# Bank_1.net
KiCad netlist of a schematic drawn in Altium Designer
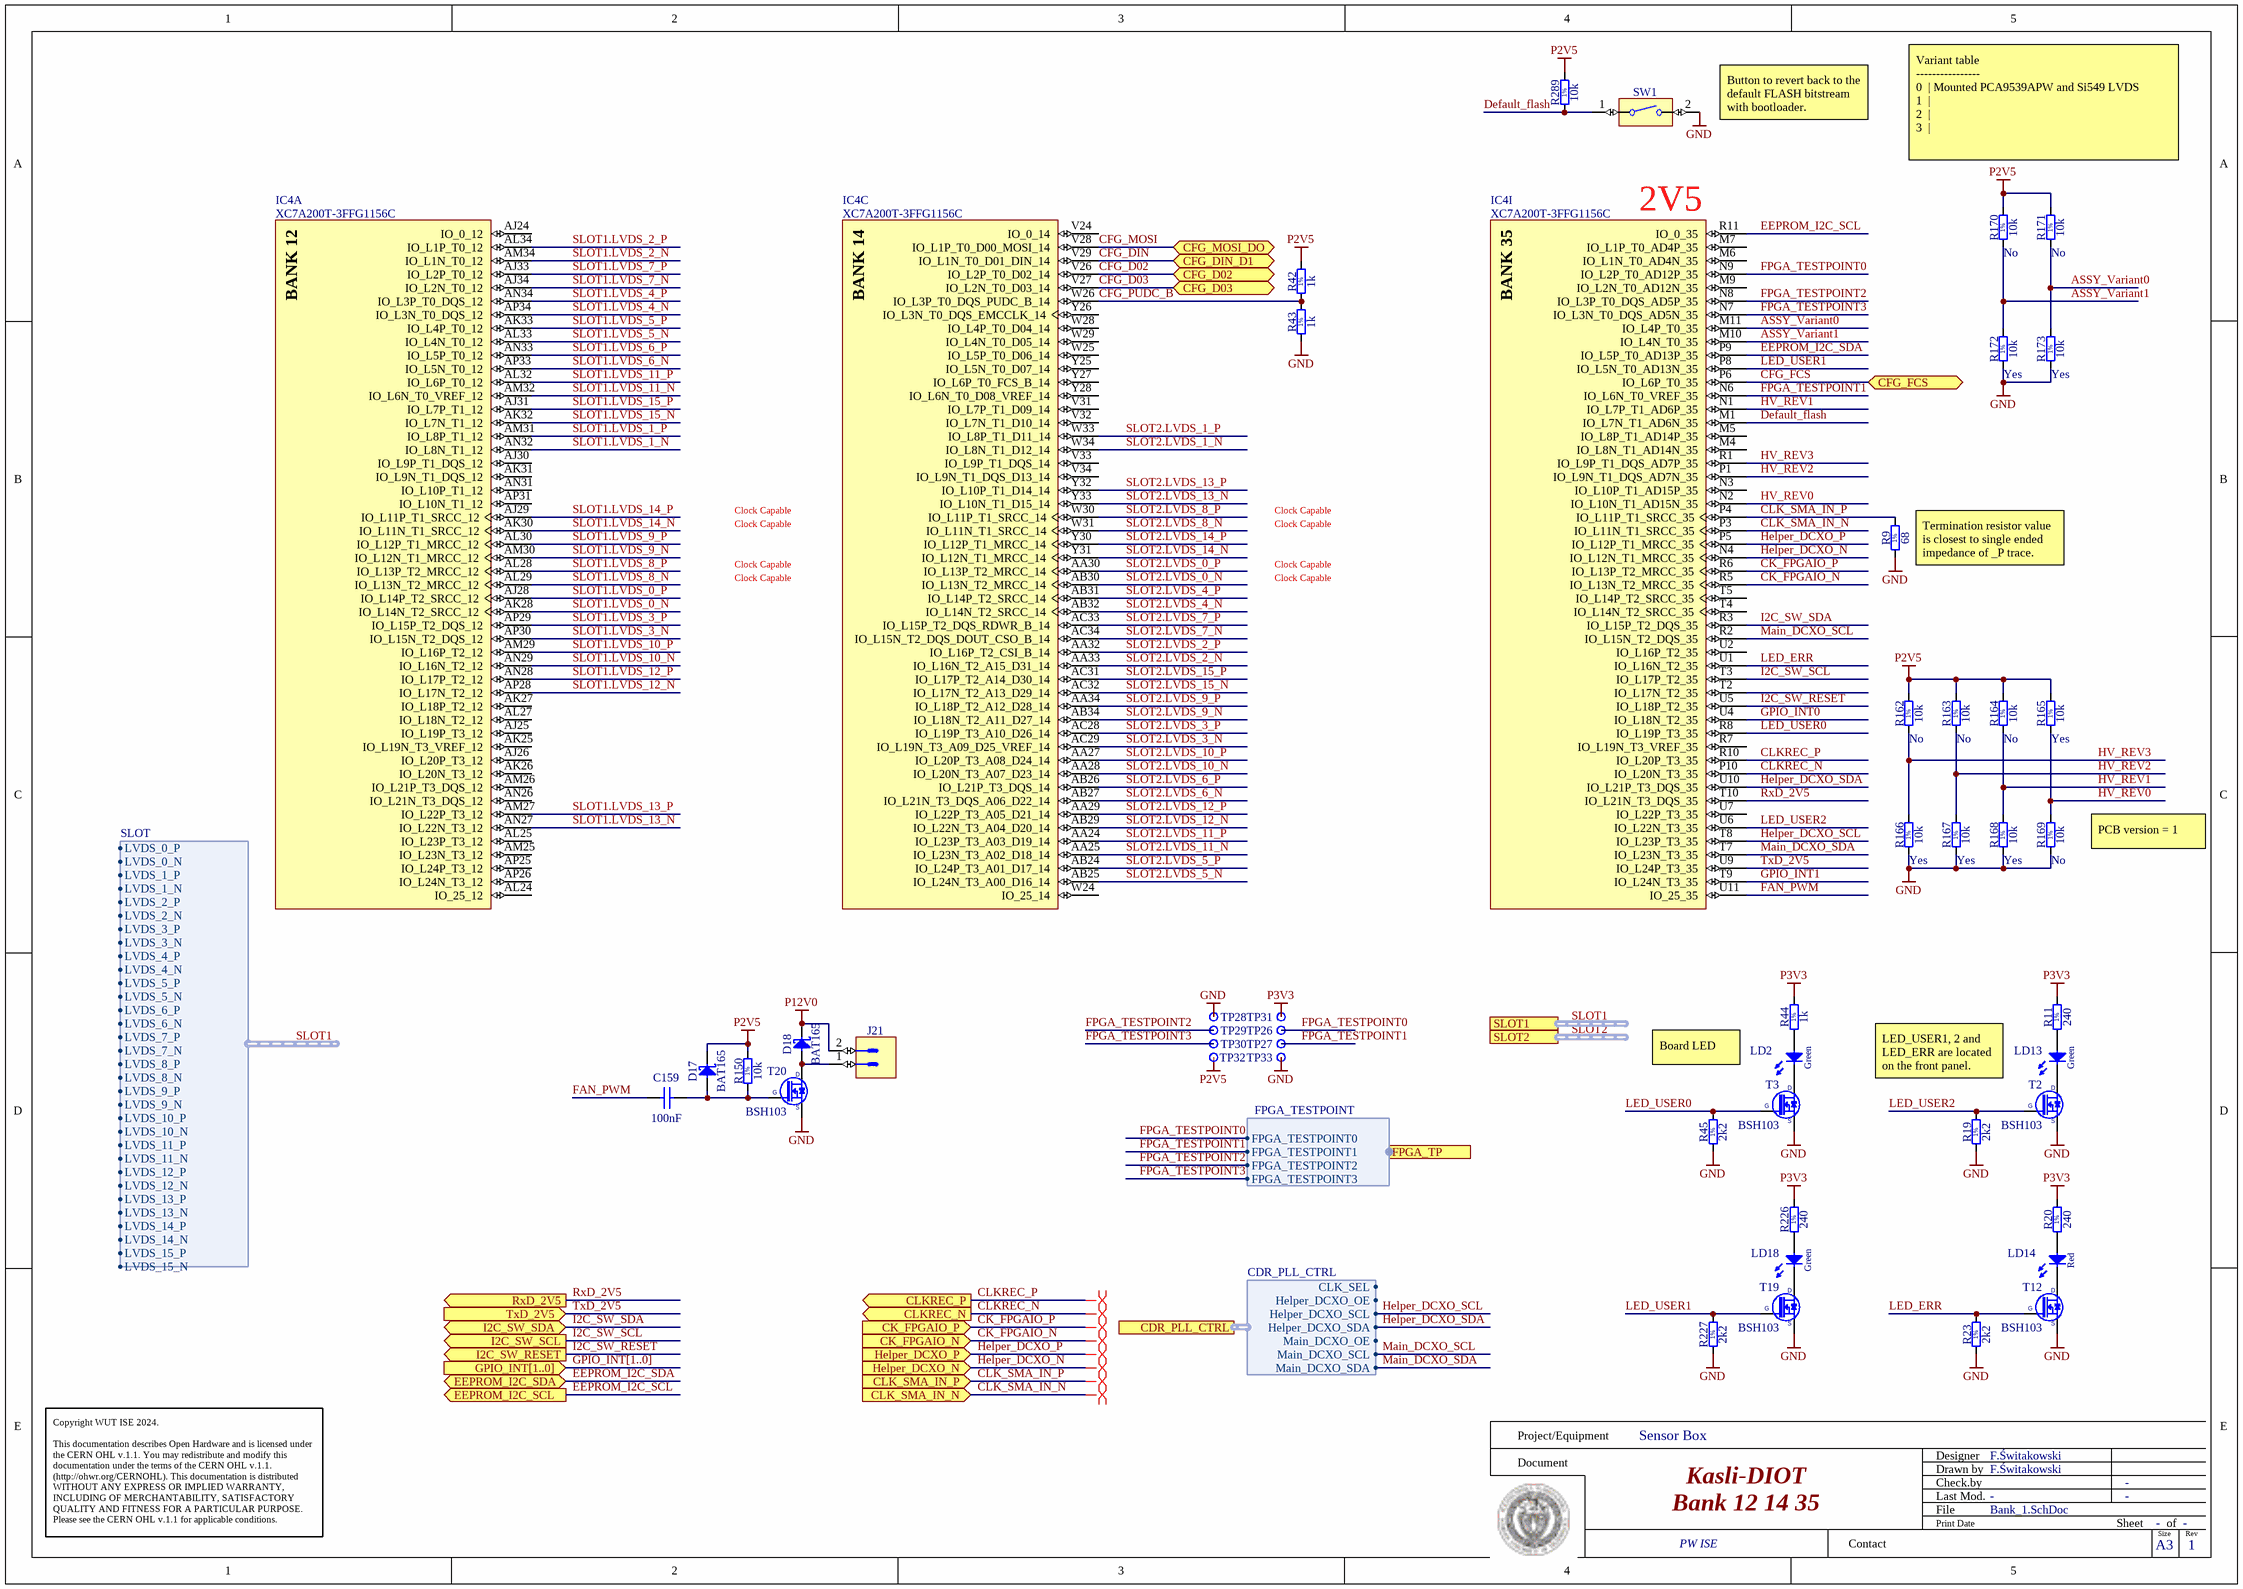
[diagram p0: Bank_1.SchDoc]

(export (version "E")
  (design (tool "Eeschema 10.0.6"))
  (components
    (comp (ref "C159")
      (value "100nF")
      (footprint "CAPC0603X33N")
      (description "Non-polarised capacitor")
      (fields
        (field (name "PART NUMBER") "CC0201_100NF_6.3V_10%_X5R")
        (field (name "VOLTAGE") "6.3V")
        (field (name "AUTHOR") "CERN DEM JLC")
      )
      (libsource (lib "Capacitors") (part "Capacitor - non polarized"))
    )
    (comp (ref "D17")
      (value "BAT165")
      (footprint "SOD2512X110N")
      (description "Schottky Diode")
      (fields
        (field (name "VOLTAGE") "40V")
        (field (name "POWER") "750mA")
        (field (name "AUTHOR") "CERN DEM JLC")
      )
      (libsource (lib "ICs And Semiconductors") (part "Diode Schottky"))
    )
    (comp (ref "D18")
      (value "BAT165")
      (footprint "SOD2512X110N")
      (description "Schottky Diode")
      (fields
        (field (name "VOLTAGE") "40V")
        (field (name "POWER") "750mA")
        (field (name "AUTHOR") "CERN DEM JLC")
      )
      (libsource (lib "ICs And Semiconductors") (part "Diode Schottky"))
    )
    (comp (ref "IC4")
      (value "XC7A200T-3FFG1156C")
      (footprint "BGA1156C100P34X34_3500X3500X310")
      (description "Artix-7 FPGA, 500 User I/Os, 16 GTP, 1156-Ball BGA, , Speed Grade 3, Commercial Grade, Pb-Free")
      (fields (field (name "MANUFACTURER") "XILINX") (field (name "AUTHOR") "CERN DEM JLC"))
      (libsource (lib "ICs And Semiconductors") (part "XC7A200T-3FFG1156C"))
    )
    (comp (ref "J21")
      (value "KK®")
      (footprint "MOLEX_22-27-2021")
      (description "Connector 2 Male")
      (fields
        (field (name "PART NUMBER") "MOLEX_22-27-2021")
        (field (name "MANUFACTURER") "MOLEX")
        (field (name "AUTHOR") "CERN DEM JLC")
      )
      (libsource (lib "Connectors") (part "Connector 2 Male"))
    )
    (comp (ref "LD2")
      (value "Green")
      (footprint "LED_KINGBRIGHT_KPH-1608CGCK")
      (description "LED Green 1C 2A")
      (fields
        (field (name "MANUFACTURER PART NUMBER") "KPH-1608CGCK")
        (field (name "PART NUMBER") "LED_KINGBRIGHT_KPH-1608CGCK")
        (field (name "AUTHOR") "CERN DEM JLC")
      )
      (libsource (lib "ICs And Semiconductors") (part "LED Green 1C 2A"))
    )
    (comp (ref "LD13")
      (value "Green")
      (footprint "LED_AVAGO_HSME-C120")
      (description "LED Green 1C 2A")
      (fields
        (field (name "MANUFACTURER PART NUMBER") "HSME-C120")
        (field (name "PART NUMBER") "LED_AVAGO_HSME-C120")
        (field (name "AUTHOR") "CERN DEM JMW")
      )
      (libsource (lib "ICs And Semiconductors") (part "LED Green 1C 2A"))
    )
    (comp (ref "LD14")
      (value "Red")
      (footprint "LED_AVAGO_HSMC-C120")
      (description "LED Red 1C 2A")
      (fields
        (field (name "MANUFACTURER PART NUMBER") "HSMC-C120")
        (field (name "PART NUMBER") "LED_AVAGO_HSMC-C120")
        (field (name "AUTHOR") "CERN DEM JMW")
      )
      (libsource (lib "ICs And Semiconductors") (part "LED Red 1C 2A"))
    )
    (comp (ref "LD18")
      (value "Green")
      (footprint "LED_AVAGO_HSME-C120")
      (description "LED Green 1C 2A")
      (fields
        (field (name "MANUFACTURER PART NUMBER") "HSME-C120")
        (field (name "PART NUMBER") "LED_AVAGO_HSME-C120")
        (field (name "AUTHOR") "CERN DEM JMW")
      )
      (libsource (lib "ICs And Semiconductors") (part "LED Green 1C 2A"))
    )
    (comp (ref "R9")
      (value "68")
      (footprint "RESC1005X40N")
      (description "Resistor - 1%")
      (fields
        (field (name "PART NUMBER") "R0402_68R_1%_0.0625W_100PPM")
        (field (name "POWER") "0.0625W")
        (field (name "AUTHOR") "CERN DEM JLC")
      )
      (libsource (lib "Resistors") (part "Resistor - 1%"))
    )
    (comp (ref "R11")
      (value "240")
      (footprint "RESC1005X40N")
      (description "Resistor - 1%")
      (fields
        (field (name "PART NUMBER") "R0402_240R_1%_0.0625W_100PPM")
        (field (name "POWER") "0.0625W")
        (field (name "AUTHOR") "CERN DEM JLC")
      )
      (libsource (lib "Resistors") (part "Resistor - 1%"))
    )
    (comp (ref "R19")
      (value "2k2")
      (footprint "RESC1005X40N")
      (description "Resistor - 1%")
      (fields
        (field (name "PART NUMBER") "R0402_2K2_1%_0.0625W_100PPM")
        (field (name "POWER") "0.0625W")
        (field (name "AUTHOR") "CERN DEM JLC")
      )
      (libsource (lib "Resistors") (part "Resistor - 1%"))
    )
    (comp (ref "R20")
      (value "240")
      (footprint "RESC1005X40N")
      (description "Resistor - 1%")
      (fields
        (field (name "PART NUMBER") "R0402_240R_1%_0.0625W_100PPM")
        (field (name "POWER") "0.0625W")
        (field (name "AUTHOR") "CERN DEM JLC")
      )
      (libsource (lib "Resistors") (part "Resistor - 1%"))
    )
    (comp (ref "R23")
      (value "2k2")
      (footprint "RESC1005X40N")
      (description "Resistor - 1%")
      (fields
        (field (name "PART NUMBER") "R0402_2K2_1%_0.0625W_100PPM")
        (field (name "POWER") "0.0625W")
        (field (name "AUTHOR") "CERN DEM JLC")
      )
      (libsource (lib "Resistors") (part "Resistor - 1%"))
    )
    (comp (ref "R42")
      (value "1k")
      (footprint "RESC1005X40N")
      (description "Resistor - 1%")
      (fields
        (field (name "PART NUMBER") "R0402_1K_1%_0.0625W_100PPM")
        (field (name "POWER") "0.0625W")
        (field (name "AUTHOR") "CERN DEM JLC")
      )
      (libsource (lib "Resistors") (part "Resistor - 1%"))
    )
    (comp (ref "R43")
      (value "1k")
      (footprint "RESC1005X40N")
      (description "Resistor - 1%")
      (fields
        (field (name "PART NUMBER") "R0402_1K_1%_0.0625W_100PPM")
        (field (name "POWER") "0.0625W")
        (field (name "AUTHOR") "CERN DEM JLC")
      )
      (libsource (lib "Resistors") (part "Resistor - 1%"))
    )
    (comp (ref "R44")
      (value "1k")
      (footprint "RESC1005X40N")
      (description "Resistor - 1%")
      (fields
        (field (name "PART NUMBER") "R0402_1K_1%_0.0625W_100PPM")
        (field (name "POWER") "0.0625W")
        (field (name "AUTHOR") "CERN DEM JLC")
      )
      (libsource (lib "Resistors") (part "Resistor - 1%"))
    )
    (comp (ref "R45")
      (value "2k2")
      (footprint "RESC1005X40N")
      (description "Resistor - 1%")
      (fields
        (field (name "PART NUMBER") "R0402_2K2_1%_0.0625W_100PPM")
        (field (name "POWER") "0.0625W")
        (field (name "AUTHOR") "CERN DEM JLC")
      )
      (libsource (lib "Resistors") (part "Resistor - 1%"))
    )
    (comp (ref "R150")
      (value "10k")
      (footprint "RESC1005X40N")
      (description "Resistor - 1%")
      (fields
        (field (name "PART NUMBER") "R0402_10K_1%_0.0625W_100PPM")
        (field (name "POWER") "0.0625W")
        (field (name "AUTHOR") "CERN DEM JLC")
      )
      (libsource (lib "Resistors") (part "Resistor - 1%"))
    )
    (comp (ref "R162")
      (value "10k")
      (footprint "RESC1005X40N")
      (description "Resistor - 1%")
      (fields
        (field (name "PART NUMBER") "R0402_10K_1%_0.0625W_100PPM")
        (field (name "POWER") "0.0625W")
        (field (name "MOUNTED") "No")
        (field (name "AUTHOR") "CERN DEM JLC")
      )
      (libsource (lib "Resistors") (part "Resistor - 1%"))
    )
    (comp (ref "R163")
      (value "10k")
      (footprint "RESC1005X40N")
      (description "Resistor - 1%")
      (fields
        (field (name "PART NUMBER") "R0402_10K_1%_0.0625W_100PPM")
        (field (name "POWER") "0.0625W")
        (field (name "MOUNTED") "No")
        (field (name "AUTHOR") "CERN DEM JLC")
      )
      (libsource (lib "Resistors") (part "Resistor - 1%"))
    )
    (comp (ref "R164")
      (value "10k")
      (footprint "RESC1005X40N")
      (description "Resistor - 1%")
      (fields
        (field (name "PART NUMBER") "R0402_10K_1%_0.0625W_100PPM")
        (field (name "POWER") "0.0625W")
        (field (name "MOUNTED") "No")
        (field (name "AUTHOR") "CERN DEM JLC")
      )
      (libsource (lib "Resistors") (part "Resistor - 1%"))
    )
    (comp (ref "R165")
      (value "10k")
      (footprint "RESC1005X40N")
      (description "Resistor - 1%")
      (fields
        (field (name "PART NUMBER") "R0402_10K_1%_0.0625W_100PPM")
        (field (name "POWER") "0.0625W")
        (field (name "MOUNTED") "Yes")
        (field (name "AUTHOR") "CERN DEM JLC")
      )
      (libsource (lib "Resistors") (part "Resistor - 1%"))
    )
    (comp (ref "R166")
      (value "10k")
      (footprint "RESC1005X40N")
      (description "Resistor - 1%")
      (fields
        (field (name "PART NUMBER") "R0402_10K_1%_0.0625W_100PPM")
        (field (name "POWER") "0.0625W")
        (field (name "MOUNTED") "Yes")
        (field (name "AUTHOR") "CERN DEM JLC")
      )
      (libsource (lib "Resistors") (part "Resistor - 1%"))
    )
    (comp (ref "R167")
      (value "10k")
      (footprint "RESC1005X40N")
      (description "Resistor - 1%")
      (fields
        (field (name "PART NUMBER") "R0402_10K_1%_0.0625W_100PPM")
        (field (name "POWER") "0.0625W")
        (field (name "MOUNTED") "Yes")
        (field (name "AUTHOR") "CERN DEM JLC")
      )
      (libsource (lib "Resistors") (part "Resistor - 1%"))
    )
    (comp (ref "R168")
      (value "10k")
      (footprint "RESC1005X40N")
      (description "Resistor - 1%")
      (fields
        (field (name "PART NUMBER") "R0402_10K_1%_0.0625W_100PPM")
        (field (name "POWER") "0.0625W")
        (field (name "MOUNTED") "Yes")
        (field (name "AUTHOR") "CERN DEM JLC")
      )
      (libsource (lib "Resistors") (part "Resistor - 1%"))
    )
    (comp (ref "R169")
      (value "10k")
      (footprint "RESC1005X40N")
      (description "Resistor - 1%")
      (fields
        (field (name "PART NUMBER") "R0402_10K_1%_0.0625W_100PPM")
        (field (name "POWER") "0.0625W")
        (field (name "MOUNTED") "No")
        (field (name "AUTHOR") "CERN DEM JLC")
      )
      (libsource (lib "Resistors") (part "Resistor - 1%"))
    )
    (comp (ref "R170")
      (value "10k")
      (footprint "RESC1005X40N")
      (description "Resistor - 1%")
      (fields
        (field (name "PART NUMBER") "R0402_10K_1%_0.0625W_100PPM")
        (field (name "POWER") "0.0625W")
        (field (name "MOUNTED") "No")
        (field (name "AUTHOR") "CERN DEM JLC")
      )
      (libsource (lib "Resistors") (part "Resistor - 1%"))
    )
    (comp (ref "R171")
      (value "10k")
      (footprint "RESC1005X40N")
      (description "Resistor - 1%")
      (fields
        (field (name "PART NUMBER") "R0402_10K_1%_0.0625W_100PPM")
        (field (name "POWER") "0.0625W")
        (field (name "MOUNTED") "No")
        (field (name "AUTHOR") "CERN DEM JLC")
      )
      (libsource (lib "Resistors") (part "Resistor - 1%"))
    )
    (comp (ref "R172")
      (value "10k")
      (footprint "RESC1005X40N")
      (description "Resistor - 1%")
      (fields
        (field (name "PART NUMBER") "R0402_10K_1%_0.0625W_100PPM")
        (field (name "POWER") "0.0625W")
        (field (name "MOUNTED") "Yes")
        (field (name "AUTHOR") "CERN DEM JLC")
      )
      (libsource (lib "Resistors") (part "Resistor - 1%"))
    )
    (comp (ref "R173")
      (value "10k")
      (footprint "RESC1005X40N")
      (description "Resistor - 1%")
      (fields
        (field (name "PART NUMBER") "R0402_10K_1%_0.0625W_100PPM")
        (field (name "POWER") "0.0625W")
        (field (name "MOUNTED") "Yes")
        (field (name "AUTHOR") "CERN DEM JLC")
      )
      (libsource (lib "Resistors") (part "Resistor - 1%"))
    )
    (comp (ref "R226")
      (value "240")
      (footprint "RESC1005X40N")
      (description "Resistor - 1%")
      (fields
        (field (name "PART NUMBER") "R0402_240R_1%_0.0625W_100PPM")
        (field (name "POWER") "0.0625W")
        (field (name "AUTHOR") "CERN DEM JLC")
      )
      (libsource (lib "Resistors") (part "Resistor - 1%"))
    )
    (comp (ref "R227")
      (value "2k2")
      (footprint "RESC1005X40N")
      (description "Resistor - 1%")
      (fields
        (field (name "PART NUMBER") "R0402_2K2_1%_0.0625W_100PPM")
        (field (name "POWER") "0.0625W")
        (field (name "AUTHOR") "CERN DEM JLC")
      )
      (libsource (lib "Resistors") (part "Resistor - 1%"))
    )
    (comp (ref "R289")
      (value "10k")
      (footprint "RESC1005X40N")
      (description "Resistor - 1%")
      (fields
        (field (name "PART NUMBER") "R0402_10K_1%_0.0625W_100PPM")
        (field (name "POWER") "0.0625W")
        (field (name "AUTHOR") "CERN DEM JLC")
      )
      (libsource (lib "Resistors") (part "Resistor - 1%"))
    )
    (comp (ref "SW1")
      (value "Switch")
      (footprint "SW_OMRON_B3U-3000PM")
      (description "1 Ways SPST DIP Switch")
      (fields
        (field (name "PART NUMBER") "SW_OMRON_B3U-3000PM")
        (field (name "MANUFACTURER") "OMRON")
        (field (name "AUTHOR") "CERN DEM HF")
      )
      (libsource (lib "Eletro-mechanical") (part "SW 1x SPST DIP Switch"))
    )
    (comp (ref "T2")
      (value "BSH103")
      (footprint "SOT95P230X110-3N")
      (description "N-CHANNEL MOSFET WITH DIODE")
      (fields (field (name "MANUFACTURER") "NEXPERIA") (field (name "AUTHOR") "CERN DEM JLC"))
      (libsource (lib "ICs And Semiconductors") (part "N-MOSFET-D 1G 2S 3D"))
    )
    (comp (ref "T3")
      (value "BSH103")
      (footprint "SOT95P230X110-3N")
      (description "N-CHANNEL MOSFET WITH DIODE")
      (fields (field (name "MANUFACTURER") "NEXPERIA") (field (name "AUTHOR") "CERN DEM JLC"))
      (libsource (lib "ICs And Semiconductors") (part "N-MOSFET-D 1G 2S 3D"))
    )
    (comp (ref "T12")
      (value "BSH103")
      (footprint "SOT95P230X110-3N")
      (description "N-CHANNEL MOSFET WITH DIODE")
      (fields (field (name "MANUFACTURER") "NEXPERIA") (field (name "AUTHOR") "CERN DEM JLC"))
      (libsource (lib "ICs And Semiconductors") (part "N-MOSFET-D 1G 2S 3D"))
    )
    (comp (ref "T19")
      (value "BSH103")
      (footprint "SOT95P230X110-3N")
      (description "N-CHANNEL MOSFET WITH DIODE")
      (fields (field (name "MANUFACTURER") "NEXPERIA") (field (name "AUTHOR") "CERN DEM JLC"))
      (libsource (lib "ICs And Semiconductors") (part "N-MOSFET-D 1G 2S 3D"))
    )
    (comp (ref "T20")
      (value "BSH103")
      (footprint "SOT95P230X110-3N")
      (description "N-CHANNEL MOSFET WITH DIODE")
      (fields (field (name "MANUFACTURER") "NEXPERIA") (field (name "AUTHOR") "CERN DEM JLC"))
      (libsource (lib "ICs And Semiconductors") (part "N-MOSFET-D 1G 2S 3D"))
    )
    (comp (ref "TP26")
      (value "Plated Hole")
      (footprint "c170h100")
      (description "Single Terminal Socket")
      (fields (field (name "PART NUMBER") "PLATED_HOLE1.0_PAD1.7") (field (name "AUTHOR") "CERN DEM JLC"))
      (libsource (lib "Eletro-mechanical") (part "Single Terminal Socket"))
    )
    (comp (ref "TP27")
      (value "Plated Hole")
      (footprint "c170h100")
      (description "Single Terminal Socket")
      (fields (field (name "PART NUMBER") "PLATED_HOLE1.0_PAD1.7") (field (name "AUTHOR") "CERN DEM JLC"))
      (libsource (lib "Eletro-mechanical") (part "Single Terminal Socket"))
    )
    (comp (ref "TP28")
      (value "Plated Hole")
      (footprint "c170h100")
      (description "Single Terminal Socket")
      (fields (field (name "PART NUMBER") "PLATED_HOLE1.0_PAD1.7") (field (name "AUTHOR") "CERN DEM JLC"))
      (libsource (lib "Eletro-mechanical") (part "Single Terminal Socket"))
    )
    (comp (ref "TP29")
      (value "Plated Hole")
      (footprint "c170h100")
      (description "Single Terminal Socket")
      (fields (field (name "PART NUMBER") "PLATED_HOLE1.0_PAD1.7") (field (name "AUTHOR") "CERN DEM JLC"))
      (libsource (lib "Eletro-mechanical") (part "Single Terminal Socket"))
    )
    (comp (ref "TP30")
      (value "Plated Hole")
      (footprint "c170h100")
      (description "Single Terminal Socket")
      (fields (field (name "PART NUMBER") "PLATED_HOLE1.0_PAD1.7") (field (name "AUTHOR") "CERN DEM JLC"))
      (libsource (lib "Eletro-mechanical") (part "Single Terminal Socket"))
    )
    (comp (ref "TP31")
      (value "Plated Hole")
      (footprint "c170h100")
      (description "Single Terminal Socket")
      (fields (field (name "PART NUMBER") "PLATED_HOLE1.0_PAD1.7") (field (name "AUTHOR") "CERN DEM JLC"))
      (libsource (lib "Eletro-mechanical") (part "Single Terminal Socket"))
    )
    (comp (ref "TP32")
      (value "Plated Hole")
      (footprint "c170h100")
      (description "Single Terminal Socket")
      (fields (field (name "PART NUMBER") "PLATED_HOLE1.0_PAD1.7") (field (name "AUTHOR") "CERN DEM JLC"))
      (libsource (lib "Eletro-mechanical") (part "Single Terminal Socket"))
    )
    (comp (ref "TP33")
      (value "Plated Hole")
      (footprint "c170h100")
      (description "Single Terminal Socket")
      (fields (field (name "PART NUMBER") "PLATED_HOLE1.0_PAD1.7") (field (name "AUTHOR") "CERN DEM JLC"))
      (libsource (lib "Eletro-mechanical") (part "Single Terminal Socket"))
    )
  )
  (nets
    (net (code "6") (name "/ASSY_Variant0") (class "Default")
      (node (ref "IC4") (pin "M11") (pinfunction "IO_L4P_T0_35_M11") (pintype "bidirectional"))
      (node (ref "R171") (pin "1") (pinfunction "1_1") (pintype "passive"))
      (node (ref "R173") (pin "2") (pinfunction "2_2") (pintype "passive"))
    )
    (net (code "7") (name "/ASSY_Variant1") (class "Default")
      (node (ref "IC4") (pin "M10") (pinfunction "IO_L4N_T0_35_M10") (pintype "bidirectional"))
      (node (ref "R170") (pin "1") (pinfunction "1_1") (pintype "passive"))
      (node (ref "R172") (pin "2") (pinfunction "2_2") (pintype "passive"))
    )
    (net (code "8") (name "/CFG_D02") (class "Default")
      (node (ref "IC4") (pin "V26") (pinfunction "IO_L2P_T0_D02_14_V26") (pintype "bidirectional"))
    )
    (net (code "9") (name "/CFG_D03") (class "Default")
      (node (ref "IC4") (pin "V27") (pinfunction "IO_L2N_T0_D03_14_V27") (pintype "bidirectional"))
    )
    (net (code "10") (name "/CFG_DIN") (class "Default")
      (node (ref "IC4") (pin "V29") (pinfunction "IO_L1N_T0_D01_DIN_14_V29") (pintype "bidirectional"))
    )
    (net (code "11") (name "/CFG_FCS") (class "Default")
      (node (ref "IC4") (pin "P6") (pinfunction "IO_L6P_T0_35_P6") (pintype "bidirectional"))
    )
    (net (code "12") (name "/CFG_MOSI") (class "Default")
      (node (ref "IC4") (pin "V28") (pinfunction "IO_L1P_T0_D00_MOSI_14_V28") (pintype "bidirectional"))
    )
    (net (code "13") (name "/CFG_PUDC_B") (class "Default")
      (node (ref "IC4") (pin "W26") (pinfunction "IO_L3P_T0_DQS_PUDC_B_14_W26") (pintype "bidirectional"))
      (node (ref "R42") (pin "1") (pinfunction "1_1") (pintype "passive"))
      (node (ref "R43") (pin "2") (pinfunction "2_2") (pintype "passive"))
    )
    (net (code "14") (name "/CK_FPGAIO_N") (class "Default")
      (node (ref "IC4") (pin "R5") (pinfunction "IO_L13N_T2_MRCC_35_R5") (pintype "bidirectional"))
    )
    (net (code "15") (name "/CK_FPGAIO_P") (class "Default")
      (node (ref "IC4") (pin "R6") (pinfunction "IO_L13P_T2_MRCC_35_R6") (pintype "bidirectional"))
    )
    (net (code "16") (name "/CLKREC_N") (class "Default")
      (node (ref "IC4") (pin "P10") (pinfunction "IO_L20N_T3_35_P10") (pintype "bidirectional"))
    )
    (net (code "17") (name "/CLKREC_P") (class "Default")
      (node (ref "IC4") (pin "R10") (pinfunction "IO_L20P_T3_35_R10") (pintype "bidirectional"))
    )
    (net (code "18") (name "/CLK_SMA_IN_N") (class "Default")
      (node (ref "IC4") (pin "P3") (pinfunction "IO_L11N_T1_SRCC_35_P3") (pintype "bidirectional"))
    )
    (net (code "19") (name "/CLK_SMA_IN_P") (class "Default")
      (node (ref "IC4") (pin "P4") (pinfunction "IO_L11P_T1_SRCC_35_P4") (pintype "bidirectional"))
      (node (ref "R9") (pin "2") (pinfunction "2_2") (pintype "passive"))
    )
    (net (code "20") (name "/Default_flash") (class "Default")
      (node (ref "IC4") (pin "M1") (pinfunction "IO_L7N_T1_AD6N_35_M1") (pintype "bidirectional"))
      (node (ref "R289") (pin "1") (pinfunction "1_1") (pintype "passive"))
      (node (ref "SW1") (pin "1") (pinfunction "1_1") (pintype "bidirectional"))
    )
    (net (code "21") (name "/EEPROM_I2C_SCL") (class "Default")
      (node (ref "IC4") (pin "R11") (pinfunction "IO_0_35_R11") (pintype "bidirectional"))
    )
    (net (code "22") (name "/EEPROM_I2C_SDA") (class "Default")
      (node (ref "IC4") (pin "P9") (pinfunction "IO_L5P_T0_AD13P_35_P9") (pintype "bidirectional"))
    )
    (net (code "23") (name "/FAN_PWM") (class "Default")
      (node (ref "C159") (pin "2") (pinfunction "2_2") (pintype "passive"))
      (node (ref "IC4") (pin "U11") (pinfunction "IO_25_35_U11") (pintype "bidirectional"))
    )
    (net (code "24") (name "/FPGA_TESTPOINT0") (class "Default")
      (node (ref "IC4") (pin "N9") (pinfunction "IO_L2P_T0_AD12P_35_N9") (pintype "bidirectional"))
      (node (ref "TP26") (pin "1") (pinfunction "1_1") (pintype "bidirectional"))
    )
    (net (code "25") (name "/FPGA_TESTPOINT1") (class "Default")
      (node (ref "IC4") (pin "N6") (pinfunction "IO_L6N_T0_VREF_35_N6") (pintype "bidirectional"))
      (node (ref "TP27") (pin "1") (pinfunction "1_1") (pintype "bidirectional"))
    )
    (net (code "26") (name "/FPGA_TESTPOINT2") (class "Default")
      (node (ref "IC4") (pin "N8") (pinfunction "IO_L3P_T0_DQS_AD5P_35_N8") (pintype "bidirectional"))
      (node (ref "TP29") (pin "1") (pinfunction "1_1") (pintype "bidirectional"))
    )
    (net (code "27") (name "/FPGA_TESTPOINT3") (class "Default")
      (node (ref "IC4") (pin "N7") (pinfunction "IO_L3N_T0_DQS_AD5N_35_N7") (pintype "bidirectional"))
      (node (ref "TP30") (pin "1") (pinfunction "1_1") (pintype "bidirectional"))
    )
    (net (code "28") (name "/GPIO_INT0") (class "Default")
      (node (ref "IC4") (pin "U4") (pinfunction "IO_L18N_T2_35_U4") (pintype "bidirectional"))
    )
    (net (code "29") (name "/GPIO_INT1") (class "Default")
      (node (ref "IC4") (pin "T9") (pinfunction "IO_L24N_T3_35_T9") (pintype "bidirectional"))
    )
    (net (code "31") (name "/HV_REV0") (class "Default")
      (node (ref "IC4") (pin "N2") (pinfunction "IO_L10N_T1_AD15N_35_N2") (pintype "bidirectional"))
      (node (ref "R165") (pin "1") (pinfunction "1_1") (pintype "passive"))
      (node (ref "R169") (pin "2") (pinfunction "2_2") (pintype "passive"))
    )
    (net (code "32") (name "/HV_REV1") (class "Default")
      (node (ref "IC4") (pin "N1") (pinfunction "IO_L7P_T1_AD6P_35_N1") (pintype "bidirectional"))
      (node (ref "R164") (pin "1") (pinfunction "1_1") (pintype "passive"))
      (node (ref "R168") (pin "2") (pinfunction "2_2") (pintype "passive"))
    )
    (net (code "33") (name "/HV_REV2") (class "Default")
      (node (ref "IC4") (pin "P1") (pinfunction "IO_L9N_T1_DQS_AD7N_35_P1") (pintype "bidirectional"))
      (node (ref "R163") (pin "1") (pinfunction "1_1") (pintype "passive"))
      (node (ref "R167") (pin "2") (pinfunction "2_2") (pintype "passive"))
    )
    (net (code "34") (name "/HV_REV3") (class "Default")
      (node (ref "IC4") (pin "R1") (pinfunction "IO_L9P_T1_DQS_AD7P_35_R1") (pintype "bidirectional"))
      (node (ref "R162") (pin "1") (pinfunction "1_1") (pintype "passive"))
      (node (ref "R166") (pin "2") (pinfunction "2_2") (pintype "passive"))
    )
    (net (code "35") (name "/Helper_DCXO_N") (class "Default")
      (node (ref "IC4") (pin "N4") (pinfunction "IO_L12N_T1_MRCC_35_N4") (pintype "bidirectional"))
    )
    (net (code "36") (name "/Helper_DCXO_P") (class "Default")
      (node (ref "IC4") (pin "P5") (pinfunction "IO_L12P_T1_MRCC_35_P5") (pintype "bidirectional"))
    )
    (net (code "37") (name "/Helper_DCXO_SCL") (class "Default")
      (node (ref "IC4") (pin "T8") (pinfunction "IO_L23P_T3_35_T8") (pintype "bidirectional"))
    )
    (net (code "38") (name "/Helper_DCXO_SDA") (class "Default")
      (node (ref "IC4") (pin "U10") (pinfunction "IO_L21P_T3_DQS_35_U10") (pintype "bidirectional"))
    )
    (net (code "39") (name "/I2C_SW_RESET") (class "Default")
      (node (ref "IC4") (pin "U5") (pinfunction "IO_L18P_T2_35_U5") (pintype "bidirectional"))
    )
    (net (code "40") (name "/I2C_SW_SCL") (class "Default")
      (node (ref "IC4") (pin "T3") (pinfunction "IO_L17P_T2_35_T3") (pintype "bidirectional"))
    )
    (net (code "41") (name "/I2C_SW_SDA") (class "Default")
      (node (ref "IC4") (pin "R3") (pinfunction "IO_L15P_T2_DQS_35_R3") (pintype "bidirectional"))
    )
    (net (code "42") (name "/LED_ERR") (class "Default")
      (node (ref "IC4") (pin "U1") (pinfunction "IO_L16N_T2_35_U1") (pintype "bidirectional"))
      (node (ref "R23") (pin "2") (pinfunction "2_2") (pintype "passive"))
      (node (ref "T12") (pin "1") (pinfunction "G_1") (pintype "passive"))
    )
    (net (code "43") (name "/LED_USER0") (class "Default")
      (node (ref "IC4") (pin "R8") (pinfunction "IO_L19P_T3_35_R8") (pintype "bidirectional"))
      (node (ref "R45") (pin "2") (pinfunction "2_2") (pintype "passive"))
      (node (ref "T3") (pin "1") (pinfunction "G_1") (pintype "passive"))
    )
    (net (code "44") (name "/LED_USER1") (class "Default")
      (node (ref "IC4") (pin "P8") (pinfunction "IO_L5N_T0_AD13N_35_P8") (pintype "bidirectional"))
      (node (ref "R227") (pin "2") (pinfunction "2_2") (pintype "passive"))
      (node (ref "T19") (pin "1") (pinfunction "G_1") (pintype "passive"))
    )
    (net (code "45") (name "/LED_USER2") (class "Default")
      (node (ref "IC4") (pin "U6") (pinfunction "IO_L22N_T3_35_U6") (pintype "bidirectional"))
      (node (ref "R19") (pin "2") (pinfunction "2_2") (pintype "passive"))
      (node (ref "T2") (pin "1") (pinfunction "G_1") (pintype "passive"))
    )
    (net (code "46") (name "/Main_DCXO_SCL") (class "Default")
      (node (ref "IC4") (pin "R2") (pinfunction "IO_L15N_T2_DQS_35_R2") (pintype "bidirectional"))
    )
    (net (code "47") (name "/Main_DCXO_SDA") (class "Default")
      (node (ref "IC4") (pin "T7") (pinfunction "IO_L23N_T3_35_T7") (pintype "bidirectional"))
    )
    (net (code "48") (name "/RxD_2V5") (class "Default")
      (node (ref "IC4") (pin "T10") (pinfunction "IO_L21N_T3_DQS_35_T10") (pintype "bidirectional"))
    )
    (net (code "49") (name "/SLOT1.LVDS_0_N") (class "Default")
      (node (ref "IC4") (pin "AK28") (pinfunction "IO_L14N_T2_SRCC_12_AK28") (pintype "bidirectional"))
    )
    (net (code "50") (name "/SLOT1.LVDS_0_P") (class "Default")
      (node (ref "IC4") (pin "AJ28") (pinfunction "IO_L14P_T2_SRCC_12_AJ28") (pintype "bidirectional"))
    )
    (net (code "51") (name "/SLOT1.LVDS_1_N") (class "Default")
      (node (ref "IC4") (pin "AN32") (pinfunction "IO_L8N_T1_12_AN32") (pintype "bidirectional"))
    )
    (net (code "52") (name "/SLOT1.LVDS_1_P") (class "Default")
      (node (ref "IC4") (pin "AM31") (pinfunction "IO_L8P_T1_12_AM31") (pintype "bidirectional"))
    )
    (net (code "53") (name "/SLOT1.LVDS_2_N") (class "Default")
      (node (ref "IC4") (pin "AM34") (pinfunction "IO_L1N_T0_12_AM34") (pintype "bidirectional"))
    )
    (net (code "54") (name "/SLOT1.LVDS_2_P") (class "Default")
      (node (ref "IC4") (pin "AL34") (pinfunction "IO_L1P_T0_12_AL34") (pintype "bidirectional"))
    )
    (net (code "55") (name "/SLOT1.LVDS_3_N") (class "Default")
      (node (ref "IC4") (pin "AP30") (pinfunction "IO_L15N_T2_DQS_12_AP30") (pintype "bidirectional"))
    )
    (net (code "56") (name "/SLOT1.LVDS_3_P") (class "Default")
      (node (ref "IC4") (pin "AP29") (pinfunction "IO_L15P_T2_DQS_12_AP29") (pintype "bidirectional"))
    )
    (net (code "57") (name "/SLOT1.LVDS_4_N") (class "Default")
      (node (ref "IC4") (pin "AP34") (pinfunction "IO_L3N_T0_DQS_12_AP34") (pintype "bidirectional"))
    )
    (net (code "58") (name "/SLOT1.LVDS_4_P") (class "Default")
      (node (ref "IC4") (pin "AN34") (pinfunction "IO_L3P_T0_DQS_12_AN34") (pintype "bidirectional"))
    )
    (net (code "59") (name "/SLOT1.LVDS_5_N") (class "Default")
      (node (ref "IC4") (pin "AL33") (pinfunction "IO_L4N_T0_12_AL33") (pintype "bidirectional"))
    )
    (net (code "60") (name "/SLOT1.LVDS_5_P") (class "Default")
      (node (ref "IC4") (pin "AK33") (pinfunction "IO_L4P_T0_12_AK33") (pintype "bidirectional"))
    )
    (net (code "61") (name "/SLOT1.LVDS_6_N") (class "Default")
      (node (ref "IC4") (pin "AP33") (pinfunction "IO_L5N_T0_12_AP33") (pintype "bidirectional"))
    )
    (net (code "62") (name "/SLOT1.LVDS_6_P") (class "Default")
      (node (ref "IC4") (pin "AN33") (pinfunction "IO_L5P_T0_12_AN33") (pintype "bidirectional"))
    )
    (net (code "63") (name "/SLOT1.LVDS_7_N") (class "Default")
      (node (ref "IC4") (pin "AJ34") (pinfunction "IO_L2N_T0_12_AJ34") (pintype "bidirectional"))
    )
    (net (code "64") (name "/SLOT1.LVDS_7_P") (class "Default")
      (node (ref "IC4") (pin "AJ33") (pinfunction "IO_L2P_T0_12_AJ33") (pintype "bidirectional"))
    )
    (net (code "65") (name "/SLOT1.LVDS_8_N") (class "Default")
      (node (ref "IC4") (pin "AL29") (pinfunction "IO_L13N_T2_MRCC_12_AL29") (pintype "bidirectional"))
    )
    (net (code "66") (name "/SLOT1.LVDS_8_P") (class "Default")
      (node (ref "IC4") (pin "AL28") (pinfunction "IO_L13P_T2_MRCC_12_AL28") (pintype "bidirectional"))
    )
    (net (code "67") (name "/SLOT1.LVDS_9_N") (class "Default")
      (node (ref "IC4") (pin "AM30") (pinfunction "IO_L12N_T1_MRCC_12_AM30") (pintype "bidirectional"))
    )
    (net (code "68") (name "/SLOT1.LVDS_9_P") (class "Default")
      (node (ref "IC4") (pin "AL30") (pinfunction "IO_L12P_T1_MRCC_12_AL30") (pintype "bidirectional"))
    )
    (net (code "69") (name "/SLOT1.LVDS_10_N") (class "Default")
      (node (ref "IC4") (pin "AN29") (pinfunction "IO_L16N_T2_12_AN29") (pintype "bidirectional"))
    )
    (net (code "70") (name "/SLOT1.LVDS_10_P") (class "Default")
      (node (ref "IC4") (pin "AM29") (pinfunction "IO_L16P_T2_12_AM29") (pintype "bidirectional"))
    )
    (net (code "71") (name "/SLOT1.LVDS_11_N") (class "Default")
      (node (ref "IC4") (pin "AM32") (pinfunction "IO_L6N_T0_VREF_12_AM32") (pintype "bidirectional"))
    )
    (net (code "72") (name "/SLOT1.LVDS_11_P") (class "Default")
      (node (ref "IC4") (pin "AL32") (pinfunction "IO_L6P_T0_12_AL32") (pintype "bidirectional"))
    )
    (net (code "73") (name "/SLOT1.LVDS_12_N") (class "Default")
      (node (ref "IC4") (pin "AP28") (pinfunction "IO_L17N_T2_12_AP28") (pintype "bidirectional"))
    )
    (net (code "74") (name "/SLOT1.LVDS_12_P") (class "Default")
      (node (ref "IC4") (pin "AN28") (pinfunction "IO_L17P_T2_12_AN28") (pintype "bidirectional"))
    )
    (net (code "75") (name "/SLOT1.LVDS_13_N") (class "Default")
      (node (ref "IC4") (pin "AN27") (pinfunction "IO_L22N_T3_12_AN27") (pintype "bidirectional"))
    )
    (net (code "76") (name "/SLOT1.LVDS_13_P") (class "Default")
      (node (ref "IC4") (pin "AM27") (pinfunction "IO_L22P_T3_12_AM27") (pintype "bidirectional"))
    )
    (net (code "77") (name "/SLOT1.LVDS_14_N") (class "Default")
      (node (ref "IC4") (pin "AK30") (pinfunction "IO_L11N_T1_SRCC_12_AK30") (pintype "bidirectional"))
    )
    (net (code "78") (name "/SLOT1.LVDS_14_P") (class "Default")
      (node (ref "IC4") (pin "AJ29") (pinfunction "IO_L11P_T1_SRCC_12_AJ29") (pintype "bidirectional"))
    )
    (net (code "79") (name "/SLOT1.LVDS_15_N") (class "Default")
      (node (ref "IC4") (pin "AK32") (pinfunction "IO_L7N_T1_12_AK32") (pintype "bidirectional"))
    )
    (net (code "80") (name "/SLOT1.LVDS_15_P") (class "Default")
      (node (ref "IC4") (pin "AJ31") (pinfunction "IO_L7P_T1_12_AJ31") (pintype "bidirectional"))
    )
    (net (code "82") (name "/SLOT2.LVDS_0_N") (class "Default")
      (node (ref "IC4") (pin "AB30") (pinfunction "IO_L13N_T2_MRCC_14_AB30") (pintype "bidirectional"))
    )
    (net (code "83") (name "/SLOT2.LVDS_0_P") (class "Default")
      (node (ref "IC4") (pin "AA30") (pinfunction "IO_L13P_T2_MRCC_14_AA30") (pintype "bidirectional"))
    )
    (net (code "84") (name "/SLOT2.LVDS_1_N") (class "Default")
      (node (ref "IC4") (pin "W34") (pinfunction "IO_L8N_T1_D12_14_W34") (pintype "bidirectional"))
    )
    (net (code "85") (name "/SLOT2.LVDS_1_P") (class "Default")
      (node (ref "IC4") (pin "W33") (pinfunction "IO_L8P_T1_D11_14_W33") (pintype "bidirectional"))
    )
    (net (code "86") (name "/SLOT2.LVDS_2_N") (class "Default")
      (node (ref "IC4") (pin "AA33") (pinfunction "IO_L16N_T2_A15_D31_14_AA33") (pintype "bidirectional"))
    )
    (net (code "87") (name "/SLOT2.LVDS_2_P") (class "Default")
      (node (ref "IC4") (pin "AA32") (pinfunction "IO_L16P_T2_CSI_B_14_AA32") (pintype "bidirectional"))
    )
    (net (code "88") (name "/SLOT2.LVDS_3_N") (class "Default")
      (node (ref "IC4") (pin "AC29") (pinfunction "IO_L19N_T3_A09_D25_VREF_14_AC29") (pintype "bidirectional"))
    )
    (net (code "89") (name "/SLOT2.LVDS_3_P") (class "Default")
      (node (ref "IC4") (pin "AC28") (pinfunction "IO_L19P_T3_A10_D26_14_AC28") (pintype "bidirectional"))
    )
    (net (code "90") (name "/SLOT2.LVDS_4_N") (class "Default")
      (node (ref "IC4") (pin "AB32") (pinfunction "IO_L14N_T2_SRCC_14_AB32") (pintype "bidirectional"))
    )
    (net (code "91") (name "/SLOT2.LVDS_4_P") (class "Default")
      (node (ref "IC4") (pin "AB31") (pinfunction "IO_L14P_T2_SRCC_14_AB31") (pintype "bidirectional"))
    )
    (net (code "92") (name "/SLOT2.LVDS_5_N") (class "Default")
      (node (ref "IC4") (pin "AB25") (pinfunction "IO_L24N_T3_A00_D16_14_AB25") (pintype "bidirectional"))
    )
    (net (code "93") (name "/SLOT2.LVDS_5_P") (class "Default")
      (node (ref "IC4") (pin "AB24") (pinfunction "IO_L24P_T3_A01_D17_14_AB24") (pintype "bidirectional"))
    )
    (net (code "94") (name "/SLOT2.LVDS_6_N") (class "Default")
      (node (ref "IC4") (pin "AB27") (pinfunction "IO_L21N_T3_DQS_A06_D22_14_AB27") (pintype "bidirectional"))
    )
    (net (code "95") (name "/SLOT2.LVDS_6_P") (class "Default")
      (node (ref "IC4") (pin "AB26") (pinfunction "IO_L21P_T3_DQS_14_AB26") (pintype "bidirectional"))
    )
    (net (code "96") (name "/SLOT2.LVDS_7_N") (class "Default")
      (node (ref "IC4") (pin "AC34") (pinfunction "IO_L15N_T2_DQS_DOUT_CSO_B_14_AC34") (pintype "bidirectional"))
    )
    (net (code "97") (name "/SLOT2.LVDS_7_P") (class "Default")
      (node (ref "IC4") (pin "AC33") (pinfunction "IO_L15P_T2_DQS_RDWR_B_14_AC33") (pintype "bidirectional"))
    )
    (net (code "98") (name "/SLOT2.LVDS_8_N") (class "Default")
      (node (ref "IC4") (pin "W31") (pinfunction "IO_L11N_T1_SRCC_14_W31") (pintype "bidirectional"))
    )
    (net (code "99") (name "/SLOT2.LVDS_8_P") (class "Default")
      (node (ref "IC4") (pin "W30") (pinfunction "IO_L11P_T1_SRCC_14_W30") (pintype "bidirectional"))
    )
    (net (code "100") (name "/SLOT2.LVDS_9_N") (class "Default")
      (node (ref "IC4") (pin "AB34") (pinfunction "IO_L18N_T2_A11_D27_14_AB34") (pintype "bidirectional"))
    )
    (net (code "101") (name "/SLOT2.LVDS_9_P") (class "Default")
      (node (ref "IC4") (pin "AA34") (pinfunction "IO_L18P_T2_A12_D28_14_AA34") (pintype "bidirectional"))
    )
    (net (code "102") (name "/SLOT2.LVDS_10_N") (class "Default")
      (node (ref "IC4") (pin "AA28") (pinfunction "IO_L20N_T3_A07_D23_14_AA28") (pintype "bidirectional"))
    )
    (net (code "103") (name "/SLOT2.LVDS_10_P") (class "Default")
      (node (ref "IC4") (pin "AA27") (pinfunction "IO_L20P_T3_A08_D24_14_AA27") (pintype "bidirectional"))
    )
    (net (code "104") (name "/SLOT2.LVDS_11_N") (class "Default")
      (node (ref "IC4") (pin "AA25") (pinfunction "IO_L23N_T3_A02_D18_14_AA25") (pintype "bidirectional"))
    )
    (net (code "105") (name "/SLOT2.LVDS_11_P") (class "Default")
      (node (ref "IC4") (pin "AA24") (pinfunction "IO_L23P_T3_A03_D19_14_AA24") (pintype "bidirectional"))
    )
    (net (code "106") (name "/SLOT2.LVDS_12_N") (class "Default")
      (node (ref "IC4") (pin "AB29") (pinfunction "IO_L22N_T3_A04_D20_14_AB29") (pintype "bidirectional"))
    )
    (net (code "107") (name "/SLOT2.LVDS_12_P") (class "Default")
      (node (ref "IC4") (pin "AA29") (pinfunction "IO_L22P_T3_A05_D21_14_AA29") (pintype "bidirectional"))
    )
    (net (code "108") (name "/SLOT2.LVDS_13_N") (class "Default")
      (node (ref "IC4") (pin "Y33") (pinfunction "IO_L10N_T1_D15_14_Y33") (pintype "bidirectional"))
    )
    (net (code "109") (name "/SLOT2.LVDS_13_P") (class "Default")
      (node (ref "IC4") (pin "Y32") (pinfunction "IO_L10P_T1_D14_14_Y32") (pintype "bidirectional"))
    )
    (net (code "110") (name "/SLOT2.LVDS_14_N") (class "Default")
      (node (ref "IC4") (pin "Y31") (pinfunction "IO_L12N_T1_MRCC_14_Y31") (pintype "bidirectional"))
    )
    (net (code "111") (name "/SLOT2.LVDS_14_P") (class "Default")
      (node (ref "IC4") (pin "Y30") (pinfunction "IO_L12P_T1_MRCC_14_Y30") (pintype "bidirectional"))
    )
    (net (code "112") (name "/SLOT2.LVDS_15_N") (class "Default")
      (node (ref "IC4") (pin "AC32") (pinfunction "IO_L17N_T2_A13_D29_14_AC32") (pintype "bidirectional"))
    )
    (net (code "113") (name "/SLOT2.LVDS_15_P") (class "Default")
      (node (ref "IC4") (pin "AC31") (pinfunction "IO_L17P_T2_A14_D30_14_AC31") (pintype "bidirectional"))
    )
    (net (code "114") (name "/TxD_2V5") (class "Default")
      (node (ref "IC4") (pin "U9") (pinfunction "IO_L24P_T3_35_U9") (pintype "bidirectional"))
    )
    (net (code "118") (name "GND") (class "Default")
      (node (ref "R166") (pin "1") (pinfunction "1_1") (pintype "passive"))
      (node (ref "R167") (pin "1") (pinfunction "1_1") (pintype "passive"))
      (node (ref "R168") (pin "1") (pinfunction "1_1") (pintype "passive"))
      (node (ref "R169") (pin "1") (pinfunction "1_1") (pintype "passive"))
      (node (ref "R172") (pin "1") (pinfunction "1_1") (pintype "passive"))
      (node (ref "R173") (pin "1") (pinfunction "1_1") (pintype "passive"))
      (node (ref "R19") (pin "1") (pinfunction "1_1") (pintype "passive"))
      (node (ref "R227") (pin "1") (pinfunction "1_1") (pintype "passive"))
      (node (ref "R23") (pin "1") (pinfunction "1_1") (pintype "passive"))
      (node (ref "R43") (pin "1") (pinfunction "1_1") (pintype "passive"))
      (node (ref "R45") (pin "1") (pinfunction "1_1") (pintype "passive"))
      (node (ref "R9") (pin "1") (pinfunction "1_1") (pintype "passive"))
      (node (ref "SW1") (pin "2") (pinfunction "2_2") (pintype "bidirectional"))
      (node (ref "T12") (pin "2") (pinfunction "S_2") (pintype "passive"))
      (node (ref "T19") (pin "2") (pinfunction "S_2") (pintype "passive"))
      (node (ref "T2") (pin "2") (pinfunction "S_2") (pintype "passive"))
      (node (ref "T20") (pin "2") (pinfunction "S_2") (pintype "passive"))
      (node (ref "T3") (pin "2") (pinfunction "S_2") (pintype "passive"))
      (node (ref "TP28") (pin "1") (pinfunction "1_1") (pintype "bidirectional"))
      (node (ref "TP33") (pin "1") (pinfunction "1_1") (pintype "bidirectional"))
    )
    (net (code "119") (name "Net-(D17-A)") (class "Default")
      (node (ref "C159") (pin "1") (pinfunction "1_1") (pintype "passive"))
      (node (ref "D17") (pin "2") (pinfunction "A_2") (pintype "passive"))
      (node (ref "R150") (pin "1") (pinfunction "1_1") (pintype "passive"))
      (node (ref "T20") (pin "1") (pinfunction "G_1") (pintype "passive"))
    )
    (net (code "120") (name "Net-(D18-A)") (class "Default")
      (node (ref "D18") (pin "2") (pinfunction "A_2") (pintype "passive"))
      (node (ref "J21") (pin "1") (pinfunction "1_1") (pintype "bidirectional"))
      (node (ref "T20") (pin "3") (pinfunction "D_3") (pintype "passive"))
    )
    (net (code "121") (name "Net-(LD2-A)") (class "Default")
      (node (ref "LD2") (pin "2") (pinfunction "A_2") (pintype "passive"))
      (node (ref "R44") (pin "1") (pinfunction "1_1") (pintype "passive"))
    )
    (net (code "122") (name "Net-(LD2-C)") (class "Default")
      (node (ref "LD2") (pin "1") (pinfunction "C_1") (pintype "passive"))
      (node (ref "T3") (pin "3") (pinfunction "D_3") (pintype "passive"))
    )
    (net (code "123") (name "Net-(LD13-A)") (class "Default")
      (node (ref "LD13") (pin "2") (pinfunction "A_2") (pintype "passive"))
      (node (ref "R11") (pin "1") (pinfunction "1_1") (pintype "passive"))
    )
    (net (code "124") (name "Net-(LD13-C)") (class "Default")
      (node (ref "LD13") (pin "1") (pinfunction "C_1") (pintype "passive"))
      (node (ref "T2") (pin "3") (pinfunction "D_3") (pintype "passive"))
    )
    (net (code "125") (name "Net-(LD14-A)") (class "Default")
      (node (ref "LD14") (pin "2") (pinfunction "A_2") (pintype "passive"))
      (node (ref "R20") (pin "1") (pinfunction "1_1") (pintype "passive"))
    )
    (net (code "126") (name "Net-(LD14-C)") (class "Default")
      (node (ref "LD14") (pin "1") (pinfunction "C_1") (pintype "passive"))
      (node (ref "T12") (pin "3") (pinfunction "D_3") (pintype "passive"))
    )
    (net (code "127") (name "Net-(LD18-A)") (class "Default")
      (node (ref "LD18") (pin "2") (pinfunction "A_2") (pintype "passive"))
      (node (ref "R226") (pin "1") (pinfunction "1_1") (pintype "passive"))
    )
    (net (code "128") (name "Net-(LD18-C)") (class "Default")
      (node (ref "LD18") (pin "1") (pinfunction "C_1") (pintype "passive"))
      (node (ref "T19") (pin "3") (pinfunction "D_3") (pintype "passive"))
    )
    (net (code "129") (name "P2V5") (class "Default")
      (node (ref "D17") (pin "1") (pinfunction "C_1") (pintype "passive"))
      (node (ref "R150") (pin "2") (pinfunction "2_2") (pintype "passive"))
      (node (ref "R162") (pin "2") (pinfunction "2_2") (pintype "passive"))
      (node (ref "R163") (pin "2") (pinfunction "2_2") (pintype "passive"))
      (node (ref "R164") (pin "2") (pinfunction "2_2") (pintype "passive"))
      (node (ref "R165") (pin "2") (pinfunction "2_2") (pintype "passive"))
      (node (ref "R170") (pin "2") (pinfunction "2_2") (pintype "passive"))
      (node (ref "R171") (pin "2") (pinfunction "2_2") (pintype "passive"))
      (node (ref "R289") (pin "2") (pinfunction "2_2") (pintype "passive"))
      (node (ref "R42") (pin "2") (pinfunction "2_2") (pintype "passive"))
      (node (ref "TP32") (pin "1") (pinfunction "1_1") (pintype "bidirectional"))
    )
    (net (code "130") (name "P3V3") (class "Default")
      (node (ref "R11") (pin "2") (pinfunction "2_2") (pintype "passive"))
      (node (ref "R20") (pin "2") (pinfunction "2_2") (pintype "passive"))
      (node (ref "R226") (pin "2") (pinfunction "2_2") (pintype "passive"))
      (node (ref "R44") (pin "2") (pinfunction "2_2") (pintype "passive"))
      (node (ref "TP31") (pin "1") (pinfunction "1_1") (pintype "bidirectional"))
    )
    (net (code "131") (name "P12V0") (class "Default")
      (node (ref "D18") (pin "1") (pinfunction "C_1") (pintype "passive"))
      (node (ref "J21") (pin "2") (pinfunction "2_2") (pintype "bidirectional"))
    )
    (net (code "132") (name "unconnected-(IC4A-IO_0_12-PadAJ24)") (class "Default")
      (node (ref "IC4") (pin "AJ24") (pinfunction "IO_0_12_AJ24") (pintype "bidirectional"))
    )
    (net (code "133") (name "unconnected-(IC4A-IO_25_12-PadAL24)") (class "Default")
      (node (ref "IC4") (pin "AL24") (pinfunction "IO_25_12_AL24") (pintype "bidirectional"))
    )
    (net (code "134") (name "unconnected-(IC4A-IO_L9N_T1_DQS_12-PadAK31)") (class "Default")
      (node (ref "IC4") (pin "AK31") (pinfunction "IO_L9N_T1_DQS_12_AK31") (pintype "bidirectional"))
    )
    (net (code "135") (name "unconnected-(IC4A-IO_L9P_T1_DQS_12-PadAJ30)") (class "Default")
      (node (ref "IC4") (pin "AJ30") (pinfunction "IO_L9P_T1_DQS_12_AJ30") (pintype "bidirectional"))
    )
    (net (code "136") (name "unconnected-(IC4A-IO_L10N_T1_12-PadAP31)") (class "Default")
      (node (ref "IC4") (pin "AP31") (pinfunction "IO_L10N_T1_12_AP31") (pintype "bidirectional"))
    )
    (net (code "137") (name "unconnected-(IC4A-IO_L10P_T1_12-PadAN31)") (class "Default")
      (node (ref "IC4") (pin "AN31") (pinfunction "IO_L10P_T1_12_AN31") (pintype "bidirectional"))
    )
    (net (code "138") (name "unconnected-(IC4A-IO_L18N_T2_12-PadAL27)") (class "Default")
      (node (ref "IC4") (pin "AL27") (pinfunction "IO_L18N_T2_12_AL27") (pintype "bidirectional"))
    )
    (net (code "139") (name "unconnected-(IC4A-IO_L18P_T2_12-PadAK27)") (class "Default")
      (node (ref "IC4") (pin "AK27") (pinfunction "IO_L18P_T2_12_AK27") (pintype "bidirectional"))
    )
    (net (code "140") (name "unconnected-(IC4A-IO_L19N_T3_VREF_12-PadAK25)") (class "Default")
      (node (ref "IC4") (pin "AK25") (pinfunction "IO_L19N_T3_VREF_12_AK25") (pintype "bidirectional"))
    )
    (net (code "141") (name "unconnected-(IC4A-IO_L19P_T3_12-PadAJ25)") (class "Default")
      (node (ref "IC4") (pin "AJ25") (pinfunction "IO_L19P_T3_12_AJ25") (pintype "bidirectional"))
    )
    (net (code "142") (name "unconnected-(IC4A-IO_L20N_T3_12-PadAK26)") (class "Default")
      (node (ref "IC4") (pin "AK26") (pinfunction "IO_L20N_T3_12_AK26") (pintype "bidirectional"))
    )
    (net (code "143") (name "unconnected-(IC4A-IO_L20P_T3_12-PadAJ26)") (class "Default")
      (node (ref "IC4") (pin "AJ26") (pinfunction "IO_L20P_T3_12_AJ26") (pintype "bidirectional"))
    )
    (net (code "144") (name "unconnected-(IC4A-IO_L21N_T3_DQS_12-PadAN26)") (class "Default")
      (node (ref "IC4") (pin "AN26") (pinfunction "IO_L21N_T3_DQS_12_AN26") (pintype "bidirectional"))
    )
    (net (code "145") (name "unconnected-(IC4A-IO_L21P_T3_DQS_12-PadAM26)") (class "Default")
      (node (ref "IC4") (pin "AM26") (pinfunction "IO_L21P_T3_DQS_12_AM26") (pintype "bidirectional"))
    )
    (net (code "146") (name "unconnected-(IC4A-IO_L23N_T3_12-PadAM25)") (class "Default")
      (node (ref "IC4") (pin "AM25") (pinfunction "IO_L23N_T3_12_AM25") (pintype "bidirectional"))
    )
    (net (code "147") (name "unconnected-(IC4A-IO_L23P_T3_12-PadAL25)") (class "Default")
      (node (ref "IC4") (pin "AL25") (pinfunction "IO_L23P_T3_12_AL25") (pintype "bidirectional"))
    )
    (net (code "148") (name "unconnected-(IC4A-IO_L24N_T3_12-PadAP26)") (class "Default")
      (node (ref "IC4") (pin "AP26") (pinfunction "IO_L24N_T3_12_AP26") (pintype "bidirectional"))
    )
    (net (code "149") (name "unconnected-(IC4A-IO_L24P_T3_12-PadAP25)") (class "Default")
      (node (ref "IC4") (pin "AP25") (pinfunction "IO_L24P_T3_12_AP25") (pintype "bidirectional"))
    )
    (net (code "150") (name "unconnected-(IC4C-IO_0_14-PadV24)") (class "Default")
      (node (ref "IC4") (pin "V24") (pinfunction "IO_0_14_V24") (pintype "bidirectional"))
    )
    (net (code "151") (name "unconnected-(IC4C-IO_25_14-PadW24)") (class "Default")
      (node (ref "IC4") (pin "W24") (pinfunction "IO_25_14_W24") (pintype "bidirectional"))
    )
    (net (code "152") (name "unconnected-(IC4C-IO_L3N_T0_DQS_EMCCLK_14-PadY26)") (class "Default")
      (node (ref "IC4") (pin "Y26") (pinfunction "IO_L3N_T0_DQS_EMCCLK_14_Y26") (pintype "bidirectional"))
    )
    (net (code "153") (name "unconnected-(IC4C-IO_L4N_T0_D05_14-PadW29)") (class "Default")
      (node (ref "IC4") (pin "W29") (pinfunction "IO_L4N_T0_D05_14_W29") (pintype "bidirectional"))
    )
    (net (code "154") (name "unconnected-(IC4C-IO_L4P_T0_D04_14-PadW28)") (class "Default")
      (node (ref "IC4") (pin "W28") (pinfunction "IO_L4P_T0_D04_14_W28") (pintype "bidirectional"))
    )
    (net (code "155") (name "unconnected-(IC4C-IO_L5N_T0_D07_14-PadY25)") (class "Default")
      (node (ref "IC4") (pin "Y25") (pinfunction "IO_L5N_T0_D07_14_Y25") (pintype "bidirectional"))
    )
    (net (code "156") (name "unconnected-(IC4C-IO_L5P_T0_D06_14-PadW25)") (class "Default")
      (node (ref "IC4") (pin "W25") (pinfunction "IO_L5P_T0_D06_14_W25") (pintype "bidirectional"))
    )
    (net (code "157") (name "unconnected-(IC4C-IO_L6N_T0_D08_VREF_14-PadY28)") (class "Default")
      (node (ref "IC4") (pin "Y28") (pinfunction "IO_L6N_T0_D08_VREF_14_Y28") (pintype "bidirectional"))
    )
    (net (code "158") (name "unconnected-(IC4C-IO_L6P_T0_FCS_B_14-PadY27)") (class "Default")
      (node (ref "IC4") (pin "Y27") (pinfunction "IO_L6P_T0_FCS_B_14_Y27") (pintype "bidirectional"))
    )
    (net (code "159") (name "unconnected-(IC4C-IO_L7N_T1_D10_14-PadV32)") (class "Default")
      (node (ref "IC4") (pin "V32") (pinfunction "IO_L7N_T1_D10_14_V32") (pintype "bidirectional"))
    )
    (net (code "160") (name "unconnected-(IC4C-IO_L7P_T1_D09_14-PadV31)") (class "Default")
      (node (ref "IC4") (pin "V31") (pinfunction "IO_L7P_T1_D09_14_V31") (pintype "bidirectional"))
    )
    (net (code "161") (name "unconnected-(IC4C-IO_L9N_T1_DQS_D13_14-PadV34)") (class "Default")
      (node (ref "IC4") (pin "V34") (pinfunction "IO_L9N_T1_DQS_D13_14_V34") (pintype "bidirectional"))
    )
    (net (code "162") (name "unconnected-(IC4C-IO_L9P_T1_DQS_14-PadV33)") (class "Default")
      (node (ref "IC4") (pin "V33") (pinfunction "IO_L9P_T1_DQS_14_V33") (pintype "bidirectional"))
    )
    (net (code "163") (name "unconnected-(IC4I-IO_L1N_T0_AD4N_35-PadM6)") (class "Default")
      (node (ref "IC4") (pin "M6") (pinfunction "IO_L1N_T0_AD4N_35_M6") (pintype "bidirectional"))
    )
    (net (code "164") (name "unconnected-(IC4I-IO_L1P_T0_AD4P_35-PadM7)") (class "Default")
      (node (ref "IC4") (pin "M7") (pinfunction "IO_L1P_T0_AD4P_35_M7") (pintype "bidirectional"))
    )
    (net (code "165") (name "unconnected-(IC4I-IO_L2N_T0_AD12N_35-PadM9)") (class "Default")
      (node (ref "IC4") (pin "M9") (pinfunction "IO_L2N_T0_AD12N_35_M9") (pintype "bidirectional"))
    )
    (net (code "166") (name "unconnected-(IC4I-IO_L8N_T1_AD14N_35-PadM4)") (class "Default")
      (node (ref "IC4") (pin "M4") (pinfunction "IO_L8N_T1_AD14N_35_M4") (pintype "bidirectional"))
    )
    (net (code "167") (name "unconnected-(IC4I-IO_L8P_T1_AD14P_35-PadM5)") (class "Default")
      (node (ref "IC4") (pin "M5") (pinfunction "IO_L8P_T1_AD14P_35_M5") (pintype "bidirectional"))
    )
    (net (code "168") (name "unconnected-(IC4I-IO_L10P_T1_AD15P_35-PadN3)") (class "Default")
      (node (ref "IC4") (pin "N3") (pinfunction "IO_L10P_T1_AD15P_35_N3") (pintype "bidirectional"))
    )
    (net (code "169") (name "unconnected-(IC4I-IO_L14N_T2_SRCC_35-PadT4)") (class "Default")
      (node (ref "IC4") (pin "T4") (pinfunction "IO_L14N_T2_SRCC_35_T4") (pintype "bidirectional"))
    )
    (net (code "170") (name "unconnected-(IC4I-IO_L14P_T2_SRCC_35-PadT5)") (class "Default")
      (node (ref "IC4") (pin "T5") (pinfunction "IO_L14P_T2_SRCC_35_T5") (pintype "bidirectional"))
    )
    (net (code "171") (name "unconnected-(IC4I-IO_L16P_T2_35-PadU2)") (class "Default")
      (node (ref "IC4") (pin "U2") (pinfunction "IO_L16P_T2_35_U2") (pintype "bidirectional"))
    )
    (net (code "172") (name "unconnected-(IC4I-IO_L17N_T2_35-PadT2)") (class "Default")
      (node (ref "IC4") (pin "T2") (pinfunction "IO_L17N_T2_35_T2") (pintype "bidirectional"))
    )
    (net (code "173") (name "unconnected-(IC4I-IO_L19N_T3_VREF_35-PadR7)") (class "Default")
      (node (ref "IC4") (pin "R7") (pinfunction "IO_L19N_T3_VREF_35_R7") (pintype "bidirectional"))
    )
    (net (code "174") (name "unconnected-(IC4I-IO_L22P_T3_35-PadU7)") (class "Default")
      (node (ref "IC4") (pin "U7") (pinfunction "IO_L22P_T3_35_U7") (pintype "bidirectional"))
    )
  )
)
